# MatrixBoard.net
KiCad netlist of a schematic drawn in EAGLE
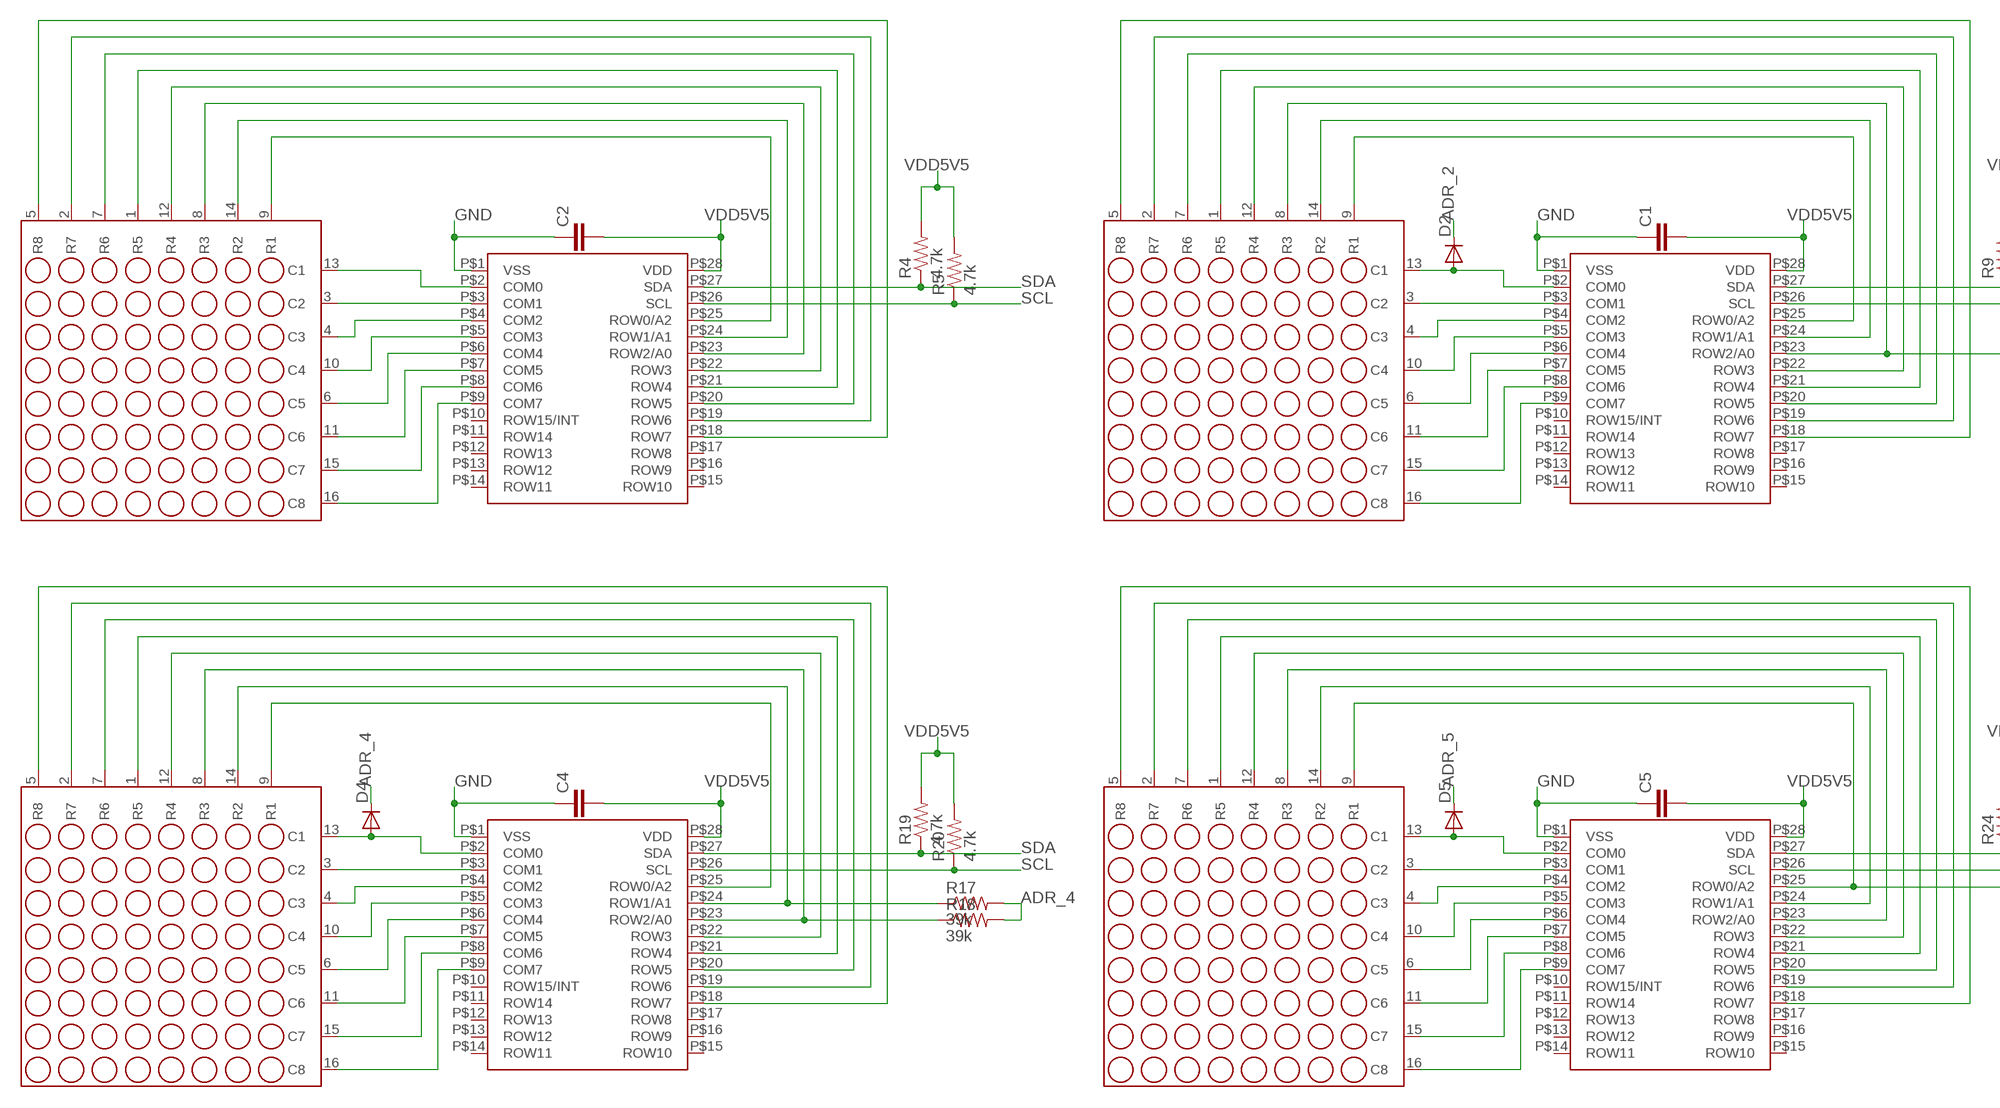
[diagram p0: schematic, sheet 1, part 1 of 2]
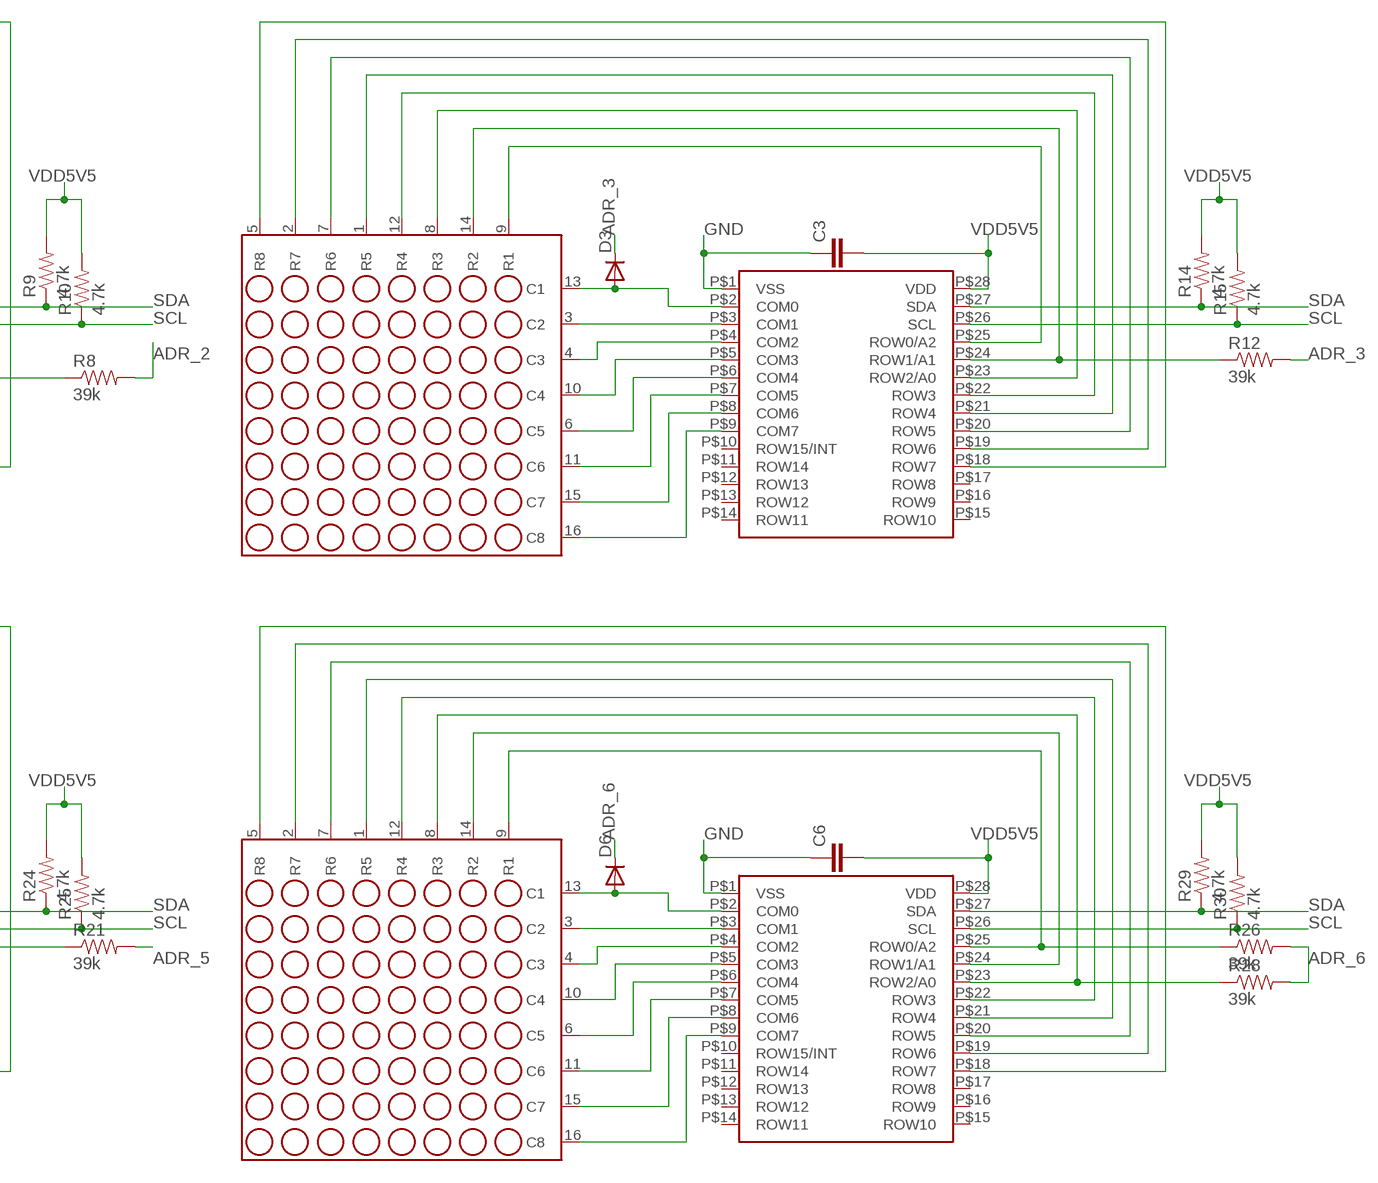
[diagram p1: schematic, sheet 1, part 2 of 2]

(export (version "E")
  (design (tool "Eeschema 10.0.6"))
  (components
    (comp (ref "C1")
      (value "CAP0805")
      (footprint "eagle-import:0805")
      (libsource (lib "eagle-import") (part "CAP0805"))
    )
    (comp (ref "C2")
      (value "CAP0805")
      (footprint "eagle-import:0805")
      (libsource (lib "eagle-import") (part "CAP0805"))
    )
    (comp (ref "C3")
      (value "CAP0805")
      (footprint "eagle-import:0805")
      (libsource (lib "eagle-import") (part "CAP0805"))
    )
    (comp (ref "C4")
      (value "CAP0805")
      (footprint "eagle-import:0805")
      (libsource (lib "eagle-import") (part "CAP0805"))
    )
    (comp (ref "C5")
      (value "CAP0805")
      (footprint "eagle-import:0805")
      (libsource (lib "eagle-import") (part "CAP0805"))
    )
    (comp (ref "C6")
      (value "CAP0805")
      (footprint "eagle-import:0805")
      (libsource (lib "eagle-import") (part "CAP0805"))
    )
    (comp (ref "D2")
      (value "DIODESMA")
      (footprint "eagle-import:SMA-DIODE")
      (libsource (lib "eagle-import") (part "DIODESMA"))
    )
    (comp (ref "D3")
      (value "DIODESMA")
      (footprint "eagle-import:SMA-DIODE")
      (libsource (lib "eagle-import") (part "DIODESMA"))
    )
    (comp (ref "D4")
      (value "DIODESMA")
      (footprint "eagle-import:SMA-DIODE")
      (libsource (lib "eagle-import") (part "DIODESMA"))
    )
    (comp (ref "D5")
      (value "DIODESMA")
      (footprint "eagle-import:SMA-DIODE")
      (libsource (lib "eagle-import") (part "DIODESMA"))
    )
    (comp (ref "D6")
      (value "DIODESMA")
      (footprint "eagle-import:SMA-DIODE")
      (libsource (lib "eagle-import") (part "DIODESMA"))
    )
    (comp (ref "R4")
      (value "4.7k")
      (footprint "eagle-import:0805")
      (libsource (lib "eagle-import") (part "RESISTOR0805-RES"))
    )
    (comp (ref "R5")
      (value "4.7k")
      (footprint "eagle-import:0805")
      (libsource (lib "eagle-import") (part "RESISTOR0805-RES"))
    )
    (comp (ref "R8")
      (value "39k")
      (footprint "eagle-import:0805")
      (libsource (lib "eagle-import") (part "RESISTOR0805-RES"))
    )
    (comp (ref "R9")
      (value "4.7k")
      (footprint "eagle-import:0805")
      (libsource (lib "eagle-import") (part "RESISTOR0805-RES"))
    )
    (comp (ref "R10")
      (value "4.7k")
      (footprint "eagle-import:0805")
      (libsource (lib "eagle-import") (part "RESISTOR0805-RES"))
    )
    (comp (ref "R12")
      (value "39k")
      (footprint "eagle-import:0805")
      (libsource (lib "eagle-import") (part "RESISTOR0805-RES"))
    )
    (comp (ref "R14")
      (value "4.7k")
      (footprint "eagle-import:0805")
      (libsource (lib "eagle-import") (part "RESISTOR0805-RES"))
    )
    (comp (ref "R15")
      (value "4.7k")
      (footprint "eagle-import:0805")
      (libsource (lib "eagle-import") (part "RESISTOR0805-RES"))
    )
    (comp (ref "R17")
      (value "39k")
      (footprint "eagle-import:0805")
      (libsource (lib "eagle-import") (part "RESISTOR0805-RES"))
    )
    (comp (ref "R18")
      (value "39k")
      (footprint "eagle-import:0805")
      (libsource (lib "eagle-import") (part "RESISTOR0805-RES"))
    )
    (comp (ref "R19")
      (value "4.7k")
      (footprint "eagle-import:0805")
      (libsource (lib "eagle-import") (part "RESISTOR0805-RES"))
    )
    (comp (ref "R20")
      (value "4.7k")
      (footprint "eagle-import:0805")
      (libsource (lib "eagle-import") (part "RESISTOR0805-RES"))
    )
    (comp (ref "R21")
      (value "39k")
      (footprint "eagle-import:0805")
      (libsource (lib "eagle-import") (part "RESISTOR0805-RES"))
    )
    (comp (ref "R24")
      (value "4.7k")
      (footprint "eagle-import:0805")
      (libsource (lib "eagle-import") (part "RESISTOR0805-RES"))
    )
    (comp (ref "R25")
      (value "4.7k")
      (footprint "eagle-import:0805")
      (libsource (lib "eagle-import") (part "RESISTOR0805-RES"))
    )
    (comp (ref "R26")
      (value "39k")
      (footprint "eagle-import:0805")
      (libsource (lib "eagle-import") (part "RESISTOR0805-RES"))
    )
    (comp (ref "R28")
      (value "39k")
      (footprint "eagle-import:0805")
      (libsource (lib "eagle-import") (part "RESISTOR0805-RES"))
    )
    (comp (ref "R29")
      (value "4.7k")
      (footprint "eagle-import:0805")
      (libsource (lib "eagle-import") (part "RESISTOR0805-RES"))
    )
    (comp (ref "R30")
      (value "4.7k")
      (footprint "eagle-import:0805")
      (libsource (lib "eagle-import") (part "RESISTOR0805-RES"))
    )
    (comp (ref "U$2")
      (value "A-788BS")
      (footprint "eagle-import:A-788BS")
      (libsource (lib "eagle-import") (part "A-788BS"))
    )
    (comp (ref "U$3")
      (value "HT16K33")
      (footprint "eagle-import:SOIC28-W")
      (libsource (lib "eagle-import") (part "HT16K33"))
    )
    (comp (ref "U$4")
      (value "A-788BS")
      (footprint "eagle-import:A-788BS")
      (libsource (lib "eagle-import") (part "A-788BS"))
    )
    (comp (ref "U$5")
      (value "HT16K33")
      (footprint "eagle-import:SOIC28-W")
      (libsource (lib "eagle-import") (part "HT16K33"))
    )
    (comp (ref "U$6")
      (value "A-788BS")
      (footprint "eagle-import:A-788BS")
      (libsource (lib "eagle-import") (part "A-788BS"))
    )
    (comp (ref "U$7")
      (value "HT16K33")
      (footprint "eagle-import:SOIC28-W")
      (libsource (lib "eagle-import") (part "HT16K33"))
    )
    (comp (ref "U$8")
      (value "A-788BS")
      (footprint "eagle-import:A-788BS")
      (libsource (lib "eagle-import") (part "A-788BS"))
    )
    (comp (ref "U$9")
      (value "HT16K33")
      (footprint "eagle-import:SOIC28-W")
      (libsource (lib "eagle-import") (part "HT16K33"))
    )
    (comp (ref "U$10")
      (value "A-788BS")
      (footprint "eagle-import:A-788BS")
      (libsource (lib "eagle-import") (part "A-788BS"))
    )
    (comp (ref "U$11")
      (value "HT16K33")
      (footprint "eagle-import:SOIC28-W")
      (libsource (lib "eagle-import") (part "HT16K33"))
    )
    (comp (ref "U$12")
      (value "A-788BS")
      (footprint "eagle-import:A-788BS")
      (libsource (lib "eagle-import") (part "A-788BS"))
    )
    (comp (ref "U$13")
      (value "HT16K33")
      (footprint "eagle-import:SOIC28-W")
      (libsource (lib "eagle-import") (part "HT16K33"))
    )
  )
  (nets
    (net (code "1") (name "/ADR_2") (class "Default")
      (node (ref "D2") (pin "C") (pinfunction "C_C") (pintype "passive"))
      (node (ref "R8") (pin "2") (pinfunction "2_2") (pintype "passive"))
    )
    (net (code "2") (name "/ADR_3") (class "Default")
      (node (ref "D3") (pin "C") (pinfunction "C_C") (pintype "passive"))
      (node (ref "R12") (pin "2") (pinfunction "2_2") (pintype "passive"))
    )
    (net (code "3") (name "/ADR_4") (class "Default")
      (node (ref "D4") (pin "C") (pinfunction "C_C") (pintype "passive"))
      (node (ref "R17") (pin "2") (pinfunction "2_2") (pintype "passive"))
      (node (ref "R18") (pin "2") (pinfunction "2_2") (pintype "passive"))
    )
    (net (code "4") (name "/ADR_5") (class "Default")
      (node (ref "D5") (pin "C") (pinfunction "C_C") (pintype "passive"))
      (node (ref "R21") (pin "2") (pinfunction "2_2") (pintype "passive"))
    )
    (net (code "5") (name "/ADR_6") (class "Default")
      (node (ref "D6") (pin "C") (pinfunction "C_C") (pintype "passive"))
      (node (ref "R26") (pin "2") (pinfunction "2_2") (pintype "passive"))
      (node (ref "R28") (pin "2") (pinfunction "2_2") (pintype "passive"))
    )
    (net (code "6") (name "/GND") (class "Default")
      (node (ref "C1") (pin "1") (pinfunction "1_1") (pintype "passive"))
      (node (ref "C2") (pin "1") (pinfunction "1_1") (pintype "passive"))
      (node (ref "C3") (pin "1") (pinfunction "1_1") (pintype "passive"))
      (node (ref "C4") (pin "1") (pinfunction "1_1") (pintype "passive"))
      (node (ref "C5") (pin "1") (pinfunction "1_1") (pintype "passive"))
      (node (ref "C6") (pin "1") (pinfunction "1_1") (pintype "passive"))
      (node (ref "U$11") (pin "P$1") (pinfunction "VSS_P$1") (pintype "bidirectional"))
      (node (ref "U$13") (pin "P$1") (pinfunction "VSS_P$1") (pintype "bidirectional"))
      (node (ref "U$3") (pin "P$1") (pinfunction "VSS_P$1") (pintype "bidirectional"))
      (node (ref "U$5") (pin "P$1") (pinfunction "VSS_P$1") (pintype "bidirectional"))
      (node (ref "U$7") (pin "P$1") (pinfunction "VSS_P$1") (pintype "bidirectional"))
      (node (ref "U$9") (pin "P$1") (pinfunction "VSS_P$1") (pintype "bidirectional"))
    )
    (net (code "7") (name "/SCL") (class "Default")
      (node (ref "R10") (pin "1") (pinfunction "1_1") (pintype "passive"))
      (node (ref "R15") (pin "1") (pinfunction "1_1") (pintype "passive"))
      (node (ref "R20") (pin "1") (pinfunction "1_1") (pintype "passive"))
      (node (ref "R25") (pin "1") (pinfunction "1_1") (pintype "passive"))
      (node (ref "R30") (pin "1") (pinfunction "1_1") (pintype "passive"))
      (node (ref "R5") (pin "1") (pinfunction "1_1") (pintype "passive"))
      (node (ref "U$11") (pin "P$26") (pinfunction "SCL_P$26") (pintype "bidirectional"))
      (node (ref "U$13") (pin "P$26") (pinfunction "SCL_P$26") (pintype "bidirectional"))
      (node (ref "U$3") (pin "P$26") (pinfunction "SCL_P$26") (pintype "bidirectional"))
      (node (ref "U$5") (pin "P$26") (pinfunction "SCL_P$26") (pintype "bidirectional"))
      (node (ref "U$7") (pin "P$26") (pinfunction "SCL_P$26") (pintype "bidirectional"))
      (node (ref "U$9") (pin "P$26") (pinfunction "SCL_P$26") (pintype "bidirectional"))
    )
    (net (code "8") (name "/SDA") (class "Default")
      (node (ref "R14") (pin "1") (pinfunction "1_1") (pintype "passive"))
      (node (ref "R19") (pin "1") (pinfunction "1_1") (pintype "passive"))
      (node (ref "R24") (pin "1") (pinfunction "1_1") (pintype "passive"))
      (node (ref "R29") (pin "1") (pinfunction "1_1") (pintype "passive"))
      (node (ref "R4") (pin "1") (pinfunction "1_1") (pintype "passive"))
      (node (ref "R9") (pin "1") (pinfunction "1_1") (pintype "passive"))
      (node (ref "U$11") (pin "P$27") (pinfunction "SDA_P$27") (pintype "bidirectional"))
      (node (ref "U$13") (pin "P$27") (pinfunction "SDA_P$27") (pintype "bidirectional"))
      (node (ref "U$3") (pin "P$27") (pinfunction "SDA_P$27") (pintype "bidirectional"))
      (node (ref "U$5") (pin "P$27") (pinfunction "SDA_P$27") (pintype "bidirectional"))
      (node (ref "U$7") (pin "P$27") (pinfunction "SDA_P$27") (pintype "bidirectional"))
      (node (ref "U$9") (pin "P$27") (pinfunction "SDA_P$27") (pintype "bidirectional"))
    )
    (net (code "9") (name "/VDD5V5") (class "Default")
      (node (ref "C1") (pin "2") (pinfunction "2_2") (pintype "passive"))
      (node (ref "C2") (pin "2") (pinfunction "2_2") (pintype "passive"))
      (node (ref "C3") (pin "2") (pinfunction "2_2") (pintype "passive"))
      (node (ref "C4") (pin "2") (pinfunction "2_2") (pintype "passive"))
      (node (ref "C5") (pin "2") (pinfunction "2_2") (pintype "passive"))
      (node (ref "C6") (pin "2") (pinfunction "2_2") (pintype "passive"))
      (node (ref "R10") (pin "2") (pinfunction "2_2") (pintype "passive"))
      (node (ref "R14") (pin "2") (pinfunction "2_2") (pintype "passive"))
      (node (ref "R15") (pin "2") (pinfunction "2_2") (pintype "passive"))
      (node (ref "R19") (pin "2") (pinfunction "2_2") (pintype "passive"))
      (node (ref "R20") (pin "2") (pinfunction "2_2") (pintype "passive"))
      (node (ref "R24") (pin "2") (pinfunction "2_2") (pintype "passive"))
      (node (ref "R25") (pin "2") (pinfunction "2_2") (pintype "passive"))
      (node (ref "R29") (pin "2") (pinfunction "2_2") (pintype "passive"))
      (node (ref "R30") (pin "2") (pinfunction "2_2") (pintype "passive"))
      (node (ref "R4") (pin "2") (pinfunction "2_2") (pintype "passive"))
      (node (ref "R5") (pin "2") (pinfunction "2_2") (pintype "passive"))
      (node (ref "R9") (pin "2") (pinfunction "2_2") (pintype "passive"))
      (node (ref "U$11") (pin "P$28") (pinfunction "VDD_P$28") (pintype "bidirectional"))
      (node (ref "U$13") (pin "P$28") (pinfunction "VDD_P$28") (pintype "bidirectional"))
      (node (ref "U$3") (pin "P$28") (pinfunction "VDD_P$28") (pintype "bidirectional"))
      (node (ref "U$5") (pin "P$28") (pinfunction "VDD_P$28") (pintype "bidirectional"))
      (node (ref "U$7") (pin "P$28") (pinfunction "VDD_P$28") (pintype "bidirectional"))
      (node (ref "U$9") (pin "P$28") (pinfunction "VDD_P$28") (pintype "bidirectional"))
    )
    (net (code "10") (name "Net-(U$2-C1)") (class "Default")
      (node (ref "U$2") (pin "13") (pinfunction "C1_13") (pintype "bidirectional"))
      (node (ref "U$3") (pin "P$2") (pinfunction "COM0_P$2") (pintype "bidirectional"))
    )
    (net (code "11") (name "Net-(U$2-C2)") (class "Default")
      (node (ref "U$2") (pin "3") (pinfunction "C2_3") (pintype "bidirectional"))
      (node (ref "U$3") (pin "P$3") (pinfunction "COM1_P$3") (pintype "bidirectional"))
    )
    (net (code "12") (name "Net-(U$2-C3)") (class "Default")
      (node (ref "U$2") (pin "4") (pinfunction "C3_4") (pintype "bidirectional"))
      (node (ref "U$3") (pin "P$4") (pinfunction "COM2_P$4") (pintype "bidirectional"))
    )
    (net (code "13") (name "Net-(U$2-C4)") (class "Default")
      (node (ref "U$2") (pin "10") (pinfunction "C4_10") (pintype "bidirectional"))
      (node (ref "U$3") (pin "P$5") (pinfunction "COM3_P$5") (pintype "bidirectional"))
    )
    (net (code "14") (name "Net-(U$2-C5)") (class "Default")
      (node (ref "U$2") (pin "6") (pinfunction "C5_6") (pintype "bidirectional"))
      (node (ref "U$3") (pin "P$6") (pinfunction "COM4_P$6") (pintype "bidirectional"))
    )
    (net (code "15") (name "Net-(U$2-C6)") (class "Default")
      (node (ref "U$2") (pin "11") (pinfunction "C6_11") (pintype "bidirectional"))
      (node (ref "U$3") (pin "P$7") (pinfunction "COM5_P$7") (pintype "bidirectional"))
    )
    (net (code "16") (name "Net-(U$2-C7)") (class "Default")
      (node (ref "U$2") (pin "15") (pinfunction "C7_15") (pintype "bidirectional"))
      (node (ref "U$3") (pin "P$8") (pinfunction "COM6_P$8") (pintype "bidirectional"))
    )
    (net (code "17") (name "Net-(U$2-C8)") (class "Default")
      (node (ref "U$2") (pin "16") (pinfunction "C8_16") (pintype "bidirectional"))
      (node (ref "U$3") (pin "P$9") (pinfunction "COM7_P$9") (pintype "bidirectional"))
    )
    (net (code "18") (name "Net-(U$2-R1)") (class "Default")
      (node (ref "U$2") (pin "9") (pinfunction "R1_9") (pintype "bidirectional"))
      (node (ref "U$3") (pin "P$25") (pinfunction "ROW0/A2_P$25") (pintype "bidirectional"))
    )
    (net (code "19") (name "Net-(U$2-R2)") (class "Default")
      (node (ref "U$2") (pin "14") (pinfunction "R2_14") (pintype "bidirectional"))
      (node (ref "U$3") (pin "P$24") (pinfunction "ROW1/A1_P$24") (pintype "bidirectional"))
    )
    (net (code "20") (name "Net-(U$2-R3)") (class "Default")
      (node (ref "U$2") (pin "8") (pinfunction "R3_8") (pintype "bidirectional"))
      (node (ref "U$3") (pin "P$23") (pinfunction "ROW2/A0_P$23") (pintype "bidirectional"))
    )
    (net (code "21") (name "Net-(U$2-R4)") (class "Default")
      (node (ref "U$2") (pin "12") (pinfunction "R4_12") (pintype "bidirectional"))
      (node (ref "U$3") (pin "P$22") (pinfunction "ROW3_P$22") (pintype "bidirectional"))
    )
    (net (code "22") (name "Net-(U$2-R5)") (class "Default")
      (node (ref "U$2") (pin "1") (pinfunction "R5_1") (pintype "bidirectional"))
      (node (ref "U$3") (pin "P$21") (pinfunction "ROW4_P$21") (pintype "bidirectional"))
    )
    (net (code "23") (name "Net-(U$2-R6)") (class "Default")
      (node (ref "U$2") (pin "7") (pinfunction "R6_7") (pintype "bidirectional"))
      (node (ref "U$3") (pin "P$20") (pinfunction "ROW5_P$20") (pintype "bidirectional"))
    )
    (net (code "24") (name "Net-(U$2-R7)") (class "Default")
      (node (ref "U$2") (pin "2") (pinfunction "R7_2") (pintype "bidirectional"))
      (node (ref "U$3") (pin "P$19") (pinfunction "ROW6_P$19") (pintype "bidirectional"))
    )
    (net (code "25") (name "Net-(U$2-R8)") (class "Default")
      (node (ref "U$2") (pin "5") (pinfunction "R8_5") (pintype "bidirectional"))
      (node (ref "U$3") (pin "P$18") (pinfunction "ROW7_P$18") (pintype "bidirectional"))
    )
    (net (code "26") (name "Net-(U$4-C1)") (class "Default")
      (node (ref "D2") (pin "A") (pinfunction "A_A") (pintype "passive"))
      (node (ref "U$4") (pin "13") (pinfunction "C1_13") (pintype "bidirectional"))
      (node (ref "U$5") (pin "P$2") (pinfunction "COM0_P$2") (pintype "bidirectional"))
    )
    (net (code "27") (name "Net-(U$4-C2)") (class "Default")
      (node (ref "U$4") (pin "3") (pinfunction "C2_3") (pintype "bidirectional"))
      (node (ref "U$5") (pin "P$3") (pinfunction "COM1_P$3") (pintype "bidirectional"))
    )
    (net (code "28") (name "Net-(U$4-C3)") (class "Default")
      (node (ref "U$4") (pin "4") (pinfunction "C3_4") (pintype "bidirectional"))
      (node (ref "U$5") (pin "P$4") (pinfunction "COM2_P$4") (pintype "bidirectional"))
    )
    (net (code "29") (name "Net-(U$4-C4)") (class "Default")
      (node (ref "U$4") (pin "10") (pinfunction "C4_10") (pintype "bidirectional"))
      (node (ref "U$5") (pin "P$5") (pinfunction "COM3_P$5") (pintype "bidirectional"))
    )
    (net (code "30") (name "Net-(U$4-C5)") (class "Default")
      (node (ref "U$4") (pin "6") (pinfunction "C5_6") (pintype "bidirectional"))
      (node (ref "U$5") (pin "P$6") (pinfunction "COM4_P$6") (pintype "bidirectional"))
    )
    (net (code "31") (name "Net-(U$4-C6)") (class "Default")
      (node (ref "U$4") (pin "11") (pinfunction "C6_11") (pintype "bidirectional"))
      (node (ref "U$5") (pin "P$7") (pinfunction "COM5_P$7") (pintype "bidirectional"))
    )
    (net (code "32") (name "Net-(U$4-C7)") (class "Default")
      (node (ref "U$4") (pin "15") (pinfunction "C7_15") (pintype "bidirectional"))
      (node (ref "U$5") (pin "P$8") (pinfunction "COM6_P$8") (pintype "bidirectional"))
    )
    (net (code "33") (name "Net-(U$4-C8)") (class "Default")
      (node (ref "U$4") (pin "16") (pinfunction "C8_16") (pintype "bidirectional"))
      (node (ref "U$5") (pin "P$9") (pinfunction "COM7_P$9") (pintype "bidirectional"))
    )
    (net (code "34") (name "Net-(U$4-R1)") (class "Default")
      (node (ref "U$4") (pin "9") (pinfunction "R1_9") (pintype "bidirectional"))
      (node (ref "U$5") (pin "P$25") (pinfunction "ROW0/A2_P$25") (pintype "bidirectional"))
    )
    (net (code "35") (name "Net-(U$4-R2)") (class "Default")
      (node (ref "U$4") (pin "14") (pinfunction "R2_14") (pintype "bidirectional"))
      (node (ref "U$5") (pin "P$24") (pinfunction "ROW1/A1_P$24") (pintype "bidirectional"))
    )
    (net (code "36") (name "Net-(U$4-R3)") (class "Default")
      (node (ref "R8") (pin "1") (pinfunction "1_1") (pintype "passive"))
      (node (ref "U$4") (pin "8") (pinfunction "R3_8") (pintype "bidirectional"))
      (node (ref "U$5") (pin "P$23") (pinfunction "ROW2/A0_P$23") (pintype "bidirectional"))
    )
    (net (code "37") (name "Net-(U$4-R4)") (class "Default")
      (node (ref "U$4") (pin "12") (pinfunction "R4_12") (pintype "bidirectional"))
      (node (ref "U$5") (pin "P$22") (pinfunction "ROW3_P$22") (pintype "bidirectional"))
    )
    (net (code "38") (name "Net-(U$4-R5)") (class "Default")
      (node (ref "U$4") (pin "1") (pinfunction "R5_1") (pintype "bidirectional"))
      (node (ref "U$5") (pin "P$21") (pinfunction "ROW4_P$21") (pintype "bidirectional"))
    )
    (net (code "39") (name "Net-(U$4-R6)") (class "Default")
      (node (ref "U$4") (pin "7") (pinfunction "R6_7") (pintype "bidirectional"))
      (node (ref "U$5") (pin "P$20") (pinfunction "ROW5_P$20") (pintype "bidirectional"))
    )
    (net (code "40") (name "Net-(U$4-R7)") (class "Default")
      (node (ref "U$4") (pin "2") (pinfunction "R7_2") (pintype "bidirectional"))
      (node (ref "U$5") (pin "P$19") (pinfunction "ROW6_P$19") (pintype "bidirectional"))
    )
    (net (code "41") (name "Net-(U$4-R8)") (class "Default")
      (node (ref "U$4") (pin "5") (pinfunction "R8_5") (pintype "bidirectional"))
      (node (ref "U$5") (pin "P$18") (pinfunction "ROW7_P$18") (pintype "bidirectional"))
    )
    (net (code "42") (name "Net-(U$6-C1)") (class "Default")
      (node (ref "D3") (pin "A") (pinfunction "A_A") (pintype "passive"))
      (node (ref "U$6") (pin "13") (pinfunction "C1_13") (pintype "bidirectional"))
      (node (ref "U$7") (pin "P$2") (pinfunction "COM0_P$2") (pintype "bidirectional"))
    )
    (net (code "43") (name "Net-(U$6-C2)") (class "Default")
      (node (ref "U$6") (pin "3") (pinfunction "C2_3") (pintype "bidirectional"))
      (node (ref "U$7") (pin "P$3") (pinfunction "COM1_P$3") (pintype "bidirectional"))
    )
    (net (code "44") (name "Net-(U$6-C3)") (class "Default")
      (node (ref "U$6") (pin "4") (pinfunction "C3_4") (pintype "bidirectional"))
      (node (ref "U$7") (pin "P$4") (pinfunction "COM2_P$4") (pintype "bidirectional"))
    )
    (net (code "45") (name "Net-(U$6-C4)") (class "Default")
      (node (ref "U$6") (pin "10") (pinfunction "C4_10") (pintype "bidirectional"))
      (node (ref "U$7") (pin "P$5") (pinfunction "COM3_P$5") (pintype "bidirectional"))
    )
    (net (code "46") (name "Net-(U$6-C5)") (class "Default")
      (node (ref "U$6") (pin "6") (pinfunction "C5_6") (pintype "bidirectional"))
      (node (ref "U$7") (pin "P$6") (pinfunction "COM4_P$6") (pintype "bidirectional"))
    )
    (net (code "47") (name "Net-(U$6-C6)") (class "Default")
      (node (ref "U$6") (pin "11") (pinfunction "C6_11") (pintype "bidirectional"))
      (node (ref "U$7") (pin "P$7") (pinfunction "COM5_P$7") (pintype "bidirectional"))
    )
    (net (code "48") (name "Net-(U$6-C7)") (class "Default")
      (node (ref "U$6") (pin "15") (pinfunction "C7_15") (pintype "bidirectional"))
      (node (ref "U$7") (pin "P$8") (pinfunction "COM6_P$8") (pintype "bidirectional"))
    )
    (net (code "49") (name "Net-(U$6-C8)") (class "Default")
      (node (ref "U$6") (pin "16") (pinfunction "C8_16") (pintype "bidirectional"))
      (node (ref "U$7") (pin "P$9") (pinfunction "COM7_P$9") (pintype "bidirectional"))
    )
    (net (code "50") (name "Net-(U$6-R1)") (class "Default")
      (node (ref "U$6") (pin "9") (pinfunction "R1_9") (pintype "bidirectional"))
      (node (ref "U$7") (pin "P$25") (pinfunction "ROW0/A2_P$25") (pintype "bidirectional"))
    )
    (net (code "51") (name "Net-(U$6-R2)") (class "Default")
      (node (ref "R12") (pin "1") (pinfunction "1_1") (pintype "passive"))
      (node (ref "U$6") (pin "14") (pinfunction "R2_14") (pintype "bidirectional"))
      (node (ref "U$7") (pin "P$24") (pinfunction "ROW1/A1_P$24") (pintype "bidirectional"))
    )
    (net (code "52") (name "Net-(U$6-R3)") (class "Default")
      (node (ref "U$6") (pin "8") (pinfunction "R3_8") (pintype "bidirectional"))
      (node (ref "U$7") (pin "P$23") (pinfunction "ROW2/A0_P$23") (pintype "bidirectional"))
    )
    (net (code "53") (name "Net-(U$6-R4)") (class "Default")
      (node (ref "U$6") (pin "12") (pinfunction "R4_12") (pintype "bidirectional"))
      (node (ref "U$7") (pin "P$22") (pinfunction "ROW3_P$22") (pintype "bidirectional"))
    )
    (net (code "54") (name "Net-(U$6-R5)") (class "Default")
      (node (ref "U$6") (pin "1") (pinfunction "R5_1") (pintype "bidirectional"))
      (node (ref "U$7") (pin "P$21") (pinfunction "ROW4_P$21") (pintype "bidirectional"))
    )
    (net (code "55") (name "Net-(U$6-R6)") (class "Default")
      (node (ref "U$6") (pin "7") (pinfunction "R6_7") (pintype "bidirectional"))
      (node (ref "U$7") (pin "P$20") (pinfunction "ROW5_P$20") (pintype "bidirectional"))
    )
    (net (code "56") (name "Net-(U$6-R7)") (class "Default")
      (node (ref "U$6") (pin "2") (pinfunction "R7_2") (pintype "bidirectional"))
      (node (ref "U$7") (pin "P$19") (pinfunction "ROW6_P$19") (pintype "bidirectional"))
    )
    (net (code "57") (name "Net-(U$6-R8)") (class "Default")
      (node (ref "U$6") (pin "5") (pinfunction "R8_5") (pintype "bidirectional"))
      (node (ref "U$7") (pin "P$18") (pinfunction "ROW7_P$18") (pintype "bidirectional"))
    )
    (net (code "58") (name "Net-(U$8-C1)") (class "Default")
      (node (ref "D6") (pin "A") (pinfunction "A_A") (pintype "passive"))
      (node (ref "U$8") (pin "13") (pinfunction "C1_13") (pintype "bidirectional"))
      (node (ref "U$9") (pin "P$2") (pinfunction "COM0_P$2") (pintype "bidirectional"))
    )
    (net (code "59") (name "Net-(U$8-C2)") (class "Default")
      (node (ref "U$8") (pin "3") (pinfunction "C2_3") (pintype "bidirectional"))
      (node (ref "U$9") (pin "P$3") (pinfunction "COM1_P$3") (pintype "bidirectional"))
    )
    (net (code "60") (name "Net-(U$8-C3)") (class "Default")
      (node (ref "U$8") (pin "4") (pinfunction "C3_4") (pintype "bidirectional"))
      (node (ref "U$9") (pin "P$4") (pinfunction "COM2_P$4") (pintype "bidirectional"))
    )
    (net (code "61") (name "Net-(U$8-C4)") (class "Default")
      (node (ref "U$8") (pin "10") (pinfunction "C4_10") (pintype "bidirectional"))
      (node (ref "U$9") (pin "P$5") (pinfunction "COM3_P$5") (pintype "bidirectional"))
    )
    (net (code "62") (name "Net-(U$8-C5)") (class "Default")
      (node (ref "U$8") (pin "6") (pinfunction "C5_6") (pintype "bidirectional"))
      (node (ref "U$9") (pin "P$6") (pinfunction "COM4_P$6") (pintype "bidirectional"))
    )
    (net (code "63") (name "Net-(U$8-C6)") (class "Default")
      (node (ref "U$8") (pin "11") (pinfunction "C6_11") (pintype "bidirectional"))
      (node (ref "U$9") (pin "P$7") (pinfunction "COM5_P$7") (pintype "bidirectional"))
    )
    (net (code "64") (name "Net-(U$8-C7)") (class "Default")
      (node (ref "U$8") (pin "15") (pinfunction "C7_15") (pintype "bidirectional"))
      (node (ref "U$9") (pin "P$8") (pinfunction "COM6_P$8") (pintype "bidirectional"))
    )
    (net (code "65") (name "Net-(U$8-C8)") (class "Default")
      (node (ref "U$8") (pin "16") (pinfunction "C8_16") (pintype "bidirectional"))
      (node (ref "U$9") (pin "P$9") (pinfunction "COM7_P$9") (pintype "bidirectional"))
    )
    (net (code "66") (name "Net-(U$8-R1)") (class "Default")
      (node (ref "R26") (pin "1") (pinfunction "1_1") (pintype "passive"))
      (node (ref "U$8") (pin "9") (pinfunction "R1_9") (pintype "bidirectional"))
      (node (ref "U$9") (pin "P$25") (pinfunction "ROW0/A2_P$25") (pintype "bidirectional"))
    )
    (net (code "67") (name "Net-(U$8-R2)") (class "Default")
      (node (ref "U$8") (pin "14") (pinfunction "R2_14") (pintype "bidirectional"))
      (node (ref "U$9") (pin "P$24") (pinfunction "ROW1/A1_P$24") (pintype "bidirectional"))
    )
    (net (code "68") (name "Net-(U$8-R3)") (class "Default")
      (node (ref "R28") (pin "1") (pinfunction "1_1") (pintype "passive"))
      (node (ref "U$8") (pin "8") (pinfunction "R3_8") (pintype "bidirectional"))
      (node (ref "U$9") (pin "P$23") (pinfunction "ROW2/A0_P$23") (pintype "bidirectional"))
    )
    (net (code "69") (name "Net-(U$8-R4)") (class "Default")
      (node (ref "U$8") (pin "12") (pinfunction "R4_12") (pintype "bidirectional"))
      (node (ref "U$9") (pin "P$22") (pinfunction "ROW3_P$22") (pintype "bidirectional"))
    )
    (net (code "70") (name "Net-(U$8-R5)") (class "Default")
      (node (ref "U$8") (pin "1") (pinfunction "R5_1") (pintype "bidirectional"))
      (node (ref "U$9") (pin "P$21") (pinfunction "ROW4_P$21") (pintype "bidirectional"))
    )
    (net (code "71") (name "Net-(U$8-R6)") (class "Default")
      (node (ref "U$8") (pin "7") (pinfunction "R6_7") (pintype "bidirectional"))
      (node (ref "U$9") (pin "P$20") (pinfunction "ROW5_P$20") (pintype "bidirectional"))
    )
    (net (code "72") (name "Net-(U$8-R7)") (class "Default")
      (node (ref "U$8") (pin "2") (pinfunction "R7_2") (pintype "bidirectional"))
      (node (ref "U$9") (pin "P$19") (pinfunction "ROW6_P$19") (pintype "bidirectional"))
    )
    (net (code "73") (name "Net-(U$8-R8)") (class "Default")
      (node (ref "U$8") (pin "5") (pinfunction "R8_5") (pintype "bidirectional"))
      (node (ref "U$9") (pin "P$18") (pinfunction "ROW7_P$18") (pintype "bidirectional"))
    )
    (net (code "74") (name "Net-(U$10-C1)") (class "Default")
      (node (ref "D5") (pin "A") (pinfunction "A_A") (pintype "passive"))
      (node (ref "U$10") (pin "13") (pinfunction "C1_13") (pintype "bidirectional"))
      (node (ref "U$11") (pin "P$2") (pinfunction "COM0_P$2") (pintype "bidirectional"))
    )
    (net (code "75") (name "Net-(U$10-C2)") (class "Default")
      (node (ref "U$10") (pin "3") (pinfunction "C2_3") (pintype "bidirectional"))
      (node (ref "U$11") (pin "P$3") (pinfunction "COM1_P$3") (pintype "bidirectional"))
    )
    (net (code "76") (name "Net-(U$10-C3)") (class "Default")
      (node (ref "U$10") (pin "4") (pinfunction "C3_4") (pintype "bidirectional"))
      (node (ref "U$11") (pin "P$4") (pinfunction "COM2_P$4") (pintype "bidirectional"))
    )
    (net (code "77") (name "Net-(U$10-C4)") (class "Default")
      (node (ref "U$10") (pin "10") (pinfunction "C4_10") (pintype "bidirectional"))
      (node (ref "U$11") (pin "P$5") (pinfunction "COM3_P$5") (pintype "bidirectional"))
    )
    (net (code "78") (name "Net-(U$10-C5)") (class "Default")
      (node (ref "U$10") (pin "6") (pinfunction "C5_6") (pintype "bidirectional"))
      (node (ref "U$11") (pin "P$6") (pinfunction "COM4_P$6") (pintype "bidirectional"))
    )
    (net (code "79") (name "Net-(U$10-C6)") (class "Default")
      (node (ref "U$10") (pin "11") (pinfunction "C6_11") (pintype "bidirectional"))
      (node (ref "U$11") (pin "P$7") (pinfunction "COM5_P$7") (pintype "bidirectional"))
    )
    (net (code "80") (name "Net-(U$10-C7)") (class "Default")
      (node (ref "U$10") (pin "15") (pinfunction "C7_15") (pintype "bidirectional"))
      (node (ref "U$11") (pin "P$8") (pinfunction "COM6_P$8") (pintype "bidirectional"))
    )
    (net (code "81") (name "Net-(U$10-C8)") (class "Default")
      (node (ref "U$10") (pin "16") (pinfunction "C8_16") (pintype "bidirectional"))
      (node (ref "U$11") (pin "P$9") (pinfunction "COM7_P$9") (pintype "bidirectional"))
    )
    (net (code "82") (name "Net-(U$10-R1)") (class "Default")
      (node (ref "R21") (pin "1") (pinfunction "1_1") (pintype "passive"))
      (node (ref "U$10") (pin "9") (pinfunction "R1_9") (pintype "bidirectional"))
      (node (ref "U$11") (pin "P$25") (pinfunction "ROW0/A2_P$25") (pintype "bidirectional"))
    )
    (net (code "83") (name "Net-(U$10-R2)") (class "Default")
      (node (ref "U$10") (pin "14") (pinfunction "R2_14") (pintype "bidirectional"))
      (node (ref "U$11") (pin "P$24") (pinfunction "ROW1/A1_P$24") (pintype "bidirectional"))
    )
    (net (code "84") (name "Net-(U$10-R3)") (class "Default")
      (node (ref "U$10") (pin "8") (pinfunction "R3_8") (pintype "bidirectional"))
      (node (ref "U$11") (pin "P$23") (pinfunction "ROW2/A0_P$23") (pintype "bidirectional"))
    )
    (net (code "85") (name "Net-(U$10-R4)") (class "Default")
      (node (ref "U$10") (pin "12") (pinfunction "R4_12") (pintype "bidirectional"))
      (node (ref "U$11") (pin "P$22") (pinfunction "ROW3_P$22") (pintype "bidirectional"))
    )
    (net (code "86") (name "Net-(U$10-R5)") (class "Default")
      (node (ref "U$10") (pin "1") (pinfunction "R5_1") (pintype "bidirectional"))
      (node (ref "U$11") (pin "P$21") (pinfunction "ROW4_P$21") (pintype "bidirectional"))
    )
    (net (code "87") (name "Net-(U$10-R6)") (class "Default")
      (node (ref "U$10") (pin "7") (pinfunction "R6_7") (pintype "bidirectional"))
      (node (ref "U$11") (pin "P$20") (pinfunction "ROW5_P$20") (pintype "bidirectional"))
    )
    (net (code "88") (name "Net-(U$10-R7)") (class "Default")
      (node (ref "U$10") (pin "2") (pinfunction "R7_2") (pintype "bidirectional"))
      (node (ref "U$11") (pin "P$19") (pinfunction "ROW6_P$19") (pintype "bidirectional"))
    )
    (net (code "89") (name "Net-(U$10-R8)") (class "Default")
      (node (ref "U$10") (pin "5") (pinfunction "R8_5") (pintype "bidirectional"))
      (node (ref "U$11") (pin "P$18") (pinfunction "ROW7_P$18") (pintype "bidirectional"))
    )
    (net (code "90") (name "Net-(U$12-C1)") (class "Default")
      (node (ref "D4") (pin "A") (pinfunction "A_A") (pintype "passive"))
      (node (ref "U$12") (pin "13") (pinfunction "C1_13") (pintype "bidirectional"))
      (node (ref "U$13") (pin "P$2") (pinfunction "COM0_P$2") (pintype "bidirectional"))
    )
    (net (code "91") (name "Net-(U$12-C2)") (class "Default")
      (node (ref "U$12") (pin "3") (pinfunction "C2_3") (pintype "bidirectional"))
      (node (ref "U$13") (pin "P$3") (pinfunction "COM1_P$3") (pintype "bidirectional"))
    )
    (net (code "92") (name "Net-(U$12-C3)") (class "Default")
      (node (ref "U$12") (pin "4") (pinfunction "C3_4") (pintype "bidirectional"))
      (node (ref "U$13") (pin "P$4") (pinfunction "COM2_P$4") (pintype "bidirectional"))
    )
    (net (code "93") (name "Net-(U$12-C4)") (class "Default")
      (node (ref "U$12") (pin "10") (pinfunction "C4_10") (pintype "bidirectional"))
      (node (ref "U$13") (pin "P$5") (pinfunction "COM3_P$5") (pintype "bidirectional"))
    )
    (net (code "94") (name "Net-(U$12-C5)") (class "Default")
      (node (ref "U$12") (pin "6") (pinfunction "C5_6") (pintype "bidirectional"))
      (node (ref "U$13") (pin "P$6") (pinfunction "COM4_P$6") (pintype "bidirectional"))
    )
    (net (code "95") (name "Net-(U$12-C6)") (class "Default")
      (node (ref "U$12") (pin "11") (pinfunction "C6_11") (pintype "bidirectional"))
      (node (ref "U$13") (pin "P$7") (pinfunction "COM5_P$7") (pintype "bidirectional"))
    )
    (net (code "96") (name "Net-(U$12-C7)") (class "Default")
      (node (ref "U$12") (pin "15") (pinfunction "C7_15") (pintype "bidirectional"))
      (node (ref "U$13") (pin "P$8") (pinfunction "COM6_P$8") (pintype "bidirectional"))
    )
    (net (code "97") (name "Net-(U$12-C8)") (class "Default")
      (node (ref "U$12") (pin "16") (pinfunction "C8_16") (pintype "bidirectional"))
      (node (ref "U$13") (pin "P$9") (pinfunction "COM7_P$9") (pintype "bidirectional"))
    )
    (net (code "98") (name "Net-(U$12-R1)") (class "Default")
      (node (ref "U$12") (pin "9") (pinfunction "R1_9") (pintype "bidirectional"))
      (node (ref "U$13") (pin "P$25") (pinfunction "ROW0/A2_P$25") (pintype "bidirectional"))
    )
    (net (code "99") (name "Net-(U$12-R2)") (class "Default")
      (node (ref "R17") (pin "1") (pinfunction "1_1") (pintype "passive"))
      (node (ref "U$12") (pin "14") (pinfunction "R2_14") (pintype "bidirectional"))
      (node (ref "U$13") (pin "P$24") (pinfunction "ROW1/A1_P$24") (pintype "bidirectional"))
    )
    (net (code "100") (name "Net-(U$12-R3)") (class "Default")
      (node (ref "R18") (pin "1") (pinfunction "1_1") (pintype "passive"))
      (node (ref "U$12") (pin "8") (pinfunction "R3_8") (pintype "bidirectional"))
      (node (ref "U$13") (pin "P$23") (pinfunction "ROW2/A0_P$23") (pintype "bidirectional"))
    )
    (net (code "101") (name "Net-(U$12-R4)") (class "Default")
      (node (ref "U$12") (pin "12") (pinfunction "R4_12") (pintype "bidirectional"))
      (node (ref "U$13") (pin "P$22") (pinfunction "ROW3_P$22") (pintype "bidirectional"))
    )
    (net (code "102") (name "Net-(U$12-R5)") (class "Default")
      (node (ref "U$12") (pin "1") (pinfunction "R5_1") (pintype "bidirectional"))
      (node (ref "U$13") (pin "P$21") (pinfunction "ROW4_P$21") (pintype "bidirectional"))
    )
    (net (code "103") (name "Net-(U$12-R6)") (class "Default")
      (node (ref "U$12") (pin "7") (pinfunction "R6_7") (pintype "bidirectional"))
      (node (ref "U$13") (pin "P$20") (pinfunction "ROW5_P$20") (pintype "bidirectional"))
    )
    (net (code "104") (name "Net-(U$12-R7)") (class "Default")
      (node (ref "U$12") (pin "2") (pinfunction "R7_2") (pintype "bidirectional"))
      (node (ref "U$13") (pin "P$19") (pinfunction "ROW6_P$19") (pintype "bidirectional"))
    )
    (net (code "105") (name "Net-(U$12-R8)") (class "Default")
      (node (ref "U$12") (pin "5") (pinfunction "R8_5") (pintype "bidirectional"))
      (node (ref "U$13") (pin "P$18") (pinfunction "ROW7_P$18") (pintype "bidirectional"))
    )
    (net (code "106") (name "unconnected-(U$3-ROW8-PadP$17)") (class "Default")
      (node (ref "U$3") (pin "P$17") (pinfunction "ROW8_P$17") (pintype "bidirectional"))
    )
    (net (code "107") (name "unconnected-(U$3-ROW9-PadP$16)") (class "Default")
      (node (ref "U$3") (pin "P$16") (pinfunction "ROW9_P$16") (pintype "bidirectional"))
    )
    (net (code "108") (name "unconnected-(U$3-ROW10-PadP$15)") (class "Default")
      (node (ref "U$3") (pin "P$15") (pinfunction "ROW10_P$15") (pintype "bidirectional"))
    )
    (net (code "109") (name "unconnected-(U$3-ROW11-PadP$14)") (class "Default")
      (node (ref "U$3") (pin "P$14") (pinfunction "ROW11_P$14") (pintype "bidirectional"))
    )
    (net (code "110") (name "unconnected-(U$3-ROW12-PadP$13)") (class "Default")
      (node (ref "U$3") (pin "P$13") (pinfunction "ROW12_P$13") (pintype "bidirectional"))
    )
    (net (code "111") (name "unconnected-(U$3-ROW13-PadP$12)") (class "Default")
      (node (ref "U$3") (pin "P$12") (pinfunction "ROW13_P$12") (pintype "bidirectional"))
    )
    (net (code "112") (name "unconnected-(U$3-ROW14-PadP$11)") (class "Default")
      (node (ref "U$3") (pin "P$11") (pinfunction "ROW14_P$11") (pintype "bidirectional"))
    )
    (net (code "113") (name "unconnected-(U$3-ROW15{slash}INT-PadP$10)") (class "Default")
      (node (ref "U$3") (pin "P$10") (pinfunction "ROW15/INT_P$10") (pintype "bidirectional"))
    )
    (net (code "114") (name "unconnected-(U$5-ROW8-PadP$17)") (class "Default")
      (node (ref "U$5") (pin "P$17") (pinfunction "ROW8_P$17") (pintype "bidirectional"))
    )
    (net (code "115") (name "unconnected-(U$5-ROW9-PadP$16)") (class "Default")
      (node (ref "U$5") (pin "P$16") (pinfunction "ROW9_P$16") (pintype "bidirectional"))
    )
    (net (code "116") (name "unconnected-(U$5-ROW10-PadP$15)") (class "Default")
      (node (ref "U$5") (pin "P$15") (pinfunction "ROW10_P$15") (pintype "bidirectional"))
    )
    (net (code "117") (name "unconnected-(U$5-ROW11-PadP$14)") (class "Default")
      (node (ref "U$5") (pin "P$14") (pinfunction "ROW11_P$14") (pintype "bidirectional"))
    )
    (net (code "118") (name "unconnected-(U$5-ROW12-PadP$13)") (class "Default")
      (node (ref "U$5") (pin "P$13") (pinfunction "ROW12_P$13") (pintype "bidirectional"))
    )
    (net (code "119") (name "unconnected-(U$5-ROW13-PadP$12)") (class "Default")
      (node (ref "U$5") (pin "P$12") (pinfunction "ROW13_P$12") (pintype "bidirectional"))
    )
    (net (code "120") (name "unconnected-(U$5-ROW14-PadP$11)") (class "Default")
      (node (ref "U$5") (pin "P$11") (pinfunction "ROW14_P$11") (pintype "bidirectional"))
    )
    (net (code "121") (name "unconnected-(U$5-ROW15{slash}INT-PadP$10)") (class "Default")
      (node (ref "U$5") (pin "P$10") (pinfunction "ROW15/INT_P$10") (pintype "bidirectional"))
    )
    (net (code "122") (name "unconnected-(U$7-ROW8-PadP$17)") (class "Default")
      (node (ref "U$7") (pin "P$17") (pinfunction "ROW8_P$17") (pintype "bidirectional"))
    )
    (net (code "123") (name "unconnected-(U$7-ROW9-PadP$16)") (class "Default")
      (node (ref "U$7") (pin "P$16") (pinfunction "ROW9_P$16") (pintype "bidirectional"))
    )
    (net (code "124") (name "unconnected-(U$7-ROW10-PadP$15)") (class "Default")
      (node (ref "U$7") (pin "P$15") (pinfunction "ROW10_P$15") (pintype "bidirectional"))
    )
    (net (code "125") (name "unconnected-(U$7-ROW11-PadP$14)") (class "Default")
      (node (ref "U$7") (pin "P$14") (pinfunction "ROW11_P$14") (pintype "bidirectional"))
    )
    (net (code "126") (name "unconnected-(U$7-ROW12-PadP$13)") (class "Default")
      (node (ref "U$7") (pin "P$13") (pinfunction "ROW12_P$13") (pintype "bidirectional"))
    )
    (net (code "127") (name "unconnected-(U$7-ROW13-PadP$12)") (class "Default")
      (node (ref "U$7") (pin "P$12") (pinfunction "ROW13_P$12") (pintype "bidirectional"))
    )
    (net (code "128") (name "unconnected-(U$7-ROW14-PadP$11)") (class "Default")
      (node (ref "U$7") (pin "P$11") (pinfunction "ROW14_P$11") (pintype "bidirectional"))
    )
    (net (code "129") (name "unconnected-(U$7-ROW15{slash}INT-PadP$10)") (class "Default")
      (node (ref "U$7") (pin "P$10") (pinfunction "ROW15/INT_P$10") (pintype "bidirectional"))
    )
    (net (code "130") (name "unconnected-(U$9-ROW8-PadP$17)") (class "Default")
      (node (ref "U$9") (pin "P$17") (pinfunction "ROW8_P$17") (pintype "bidirectional"))
    )
    (net (code "131") (name "unconnected-(U$9-ROW9-PadP$16)") (class "Default")
      (node (ref "U$9") (pin "P$16") (pinfunction "ROW9_P$16") (pintype "bidirectional"))
    )
    (net (code "132") (name "unconnected-(U$9-ROW10-PadP$15)") (class "Default")
      (node (ref "U$9") (pin "P$15") (pinfunction "ROW10_P$15") (pintype "bidirectional"))
    )
    (net (code "133") (name "unconnected-(U$9-ROW11-PadP$14)") (class "Default")
      (node (ref "U$9") (pin "P$14") (pinfunction "ROW11_P$14") (pintype "bidirectional"))
    )
    (net (code "134") (name "unconnected-(U$9-ROW12-PadP$13)") (class "Default")
      (node (ref "U$9") (pin "P$13") (pinfunction "ROW12_P$13") (pintype "bidirectional"))
    )
    (net (code "135") (name "unconnected-(U$9-ROW13-PadP$12)") (class "Default")
      (node (ref "U$9") (pin "P$12") (pinfunction "ROW13_P$12") (pintype "bidirectional"))
    )
    (net (code "136") (name "unconnected-(U$9-ROW14-PadP$11)") (class "Default")
      (node (ref "U$9") (pin "P$11") (pinfunction "ROW14_P$11") (pintype "bidirectional"))
    )
    (net (code "137") (name "unconnected-(U$9-ROW15{slash}INT-PadP$10)") (class "Default")
      (node (ref "U$9") (pin "P$10") (pinfunction "ROW15/INT_P$10") (pintype "bidirectional"))
    )
    (net (code "138") (name "unconnected-(U$11-ROW8-PadP$17)") (class "Default")
      (node (ref "U$11") (pin "P$17") (pinfunction "ROW8_P$17") (pintype "bidirectional"))
    )
    (net (code "139") (name "unconnected-(U$11-ROW9-PadP$16)") (class "Default")
      (node (ref "U$11") (pin "P$16") (pinfunction "ROW9_P$16") (pintype "bidirectional"))
    )
    (net (code "140") (name "unconnected-(U$11-ROW10-PadP$15)") (class "Default")
      (node (ref "U$11") (pin "P$15") (pinfunction "ROW10_P$15") (pintype "bidirectional"))
    )
    (net (code "141") (name "unconnected-(U$11-ROW11-PadP$14)") (class "Default")
      (node (ref "U$11") (pin "P$14") (pinfunction "ROW11_P$14") (pintype "bidirectional"))
    )
    (net (code "142") (name "unconnected-(U$11-ROW12-PadP$13)") (class "Default")
      (node (ref "U$11") (pin "P$13") (pinfunction "ROW12_P$13") (pintype "bidirectional"))
    )
    (net (code "143") (name "unconnected-(U$11-ROW13-PadP$12)") (class "Default")
      (node (ref "U$11") (pin "P$12") (pinfunction "ROW13_P$12") (pintype "bidirectional"))
    )
    (net (code "144") (name "unconnected-(U$11-ROW14-PadP$11)") (class "Default")
      (node (ref "U$11") (pin "P$11") (pinfunction "ROW14_P$11") (pintype "bidirectional"))
    )
    (net (code "145") (name "unconnected-(U$11-ROW15{slash}INT-PadP$10)") (class "Default")
      (node (ref "U$11") (pin "P$10") (pinfunction "ROW15/INT_P$10") (pintype "bidirectional"))
    )
    (net (code "146") (name "unconnected-(U$13-ROW8-PadP$17)") (class "Default")
      (node (ref "U$13") (pin "P$17") (pinfunction "ROW8_P$17") (pintype "bidirectional"))
    )
    (net (code "147") (name "unconnected-(U$13-ROW9-PadP$16)") (class "Default")
      (node (ref "U$13") (pin "P$16") (pinfunction "ROW9_P$16") (pintype "bidirectional"))
    )
    (net (code "148") (name "unconnected-(U$13-ROW10-PadP$15)") (class "Default")
      (node (ref "U$13") (pin "P$15") (pinfunction "ROW10_P$15") (pintype "bidirectional"))
    )
    (net (code "149") (name "unconnected-(U$13-ROW11-PadP$14)") (class "Default")
      (node (ref "U$13") (pin "P$14") (pinfunction "ROW11_P$14") (pintype "bidirectional"))
    )
    (net (code "150") (name "unconnected-(U$13-ROW12-PadP$13)") (class "Default")
      (node (ref "U$13") (pin "P$13") (pinfunction "ROW12_P$13") (pintype "bidirectional"))
    )
    (net (code "151") (name "unconnected-(U$13-ROW13-PadP$12)") (class "Default")
      (node (ref "U$13") (pin "P$12") (pinfunction "ROW13_P$12") (pintype "bidirectional"))
    )
    (net (code "152") (name "unconnected-(U$13-ROW14-PadP$11)") (class "Default")
      (node (ref "U$13") (pin "P$11") (pinfunction "ROW14_P$11") (pintype "bidirectional"))
    )
    (net (code "153") (name "unconnected-(U$13-ROW15{slash}INT-PadP$10)") (class "Default")
      (node (ref "U$13") (pin "P$10") (pinfunction "ROW15/INT_P$10") (pintype "bidirectional"))
    )
  )
)
